# mrShark_04_a.net
KiCad netlist of a schematic drawn in EAGLE
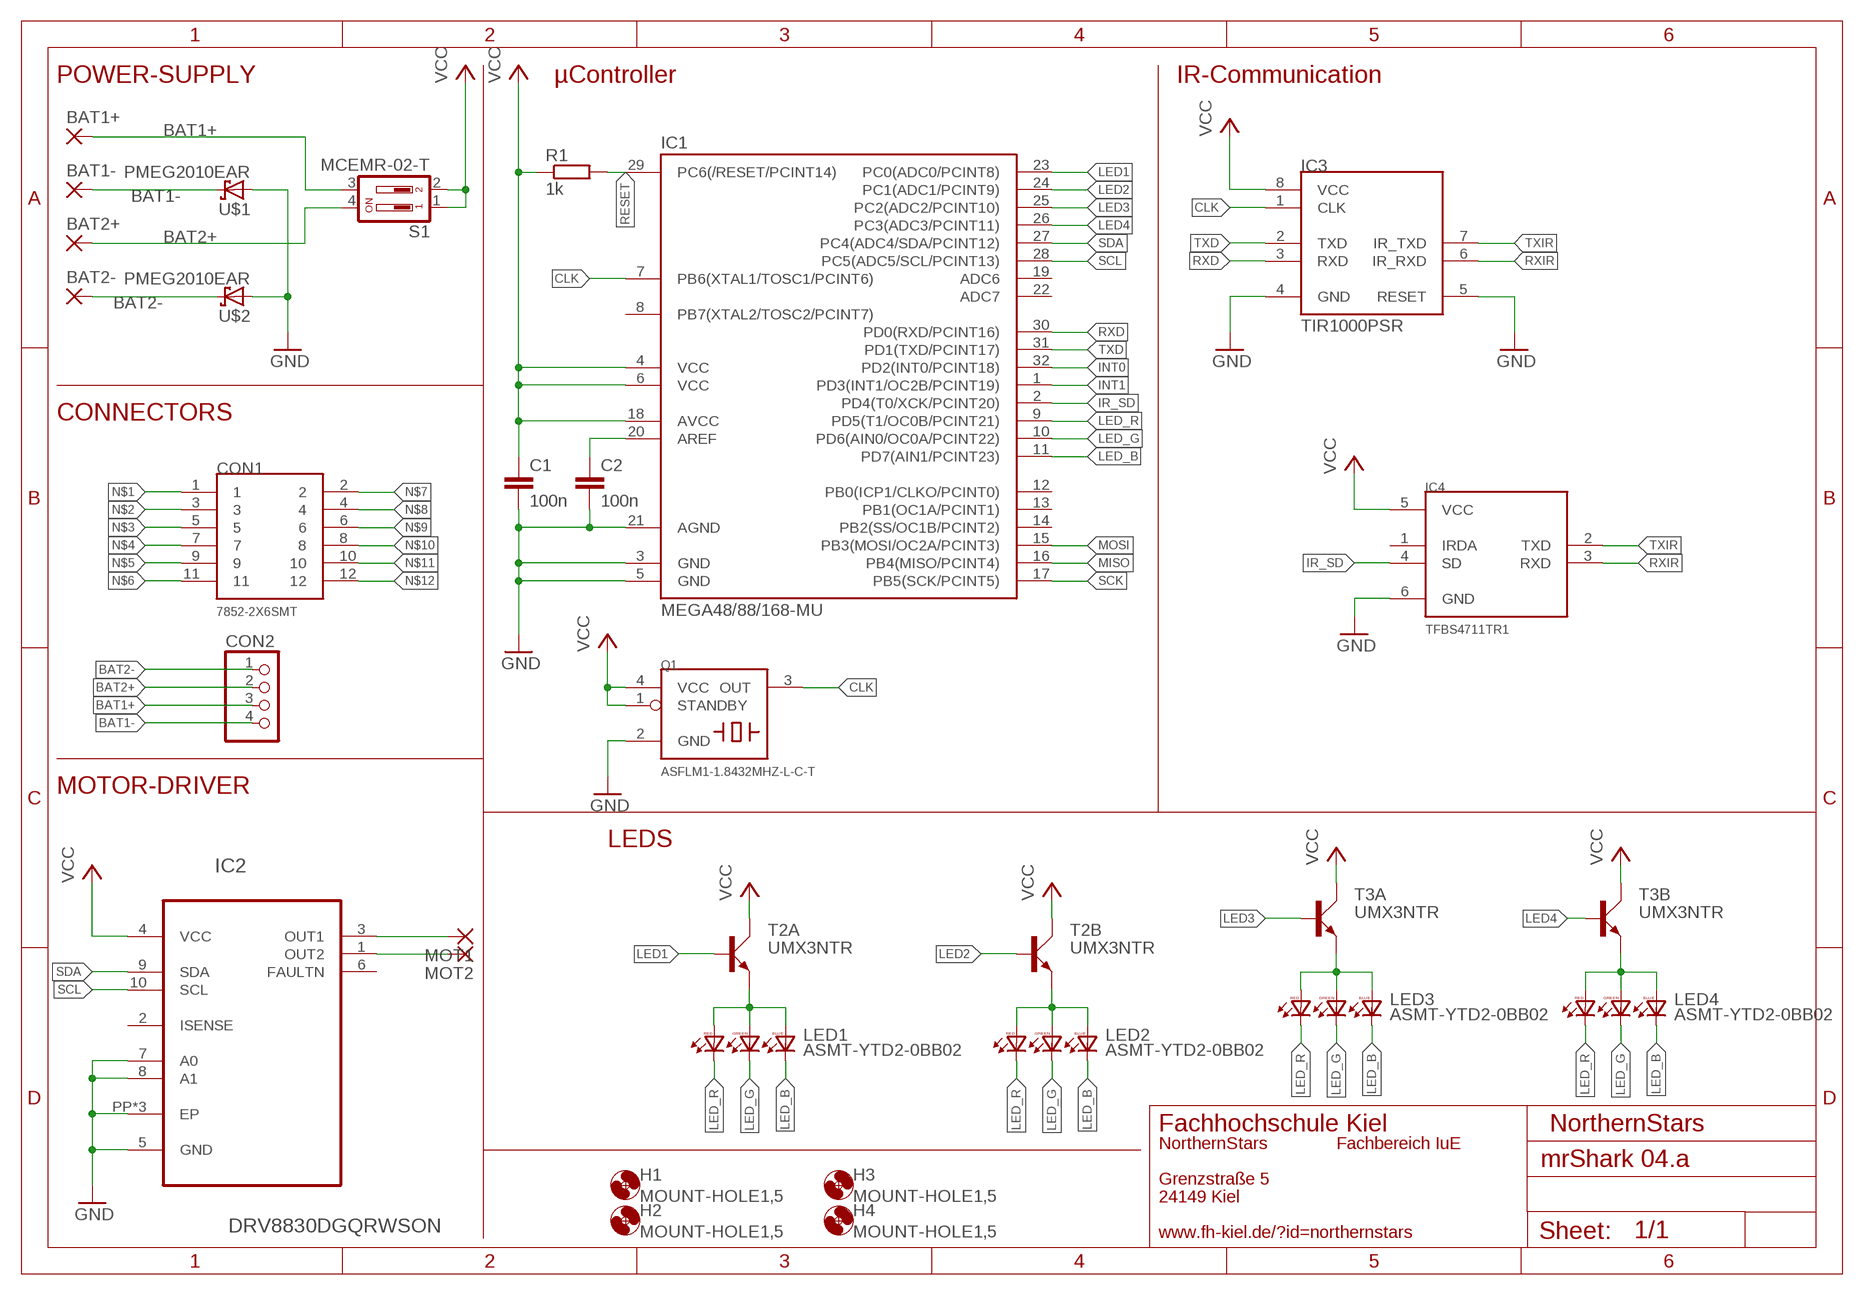
[diagram p0: schematic, sheet 1]

(export (version "E")
  (design (tool "Eeschema 10.0.6"))
  (components
    (comp (ref "BAT1+")
      (value "1,6/0,9")
      (footprint "eagle-import:1,6_0,9")
      (libsource (lib "eagle-import") (part "1,6/0,9"))
    )
    (comp (ref "BAT1-")
      (value "1,6/0,9")
      (footprint "eagle-import:1,6_0,9")
      (libsource (lib "eagle-import") (part "1,6/0,9"))
    )
    (comp (ref "BAT2+")
      (value "1,6/0,9")
      (footprint "eagle-import:1,6_0,9")
      (libsource (lib "eagle-import") (part "1,6/0,9"))
    )
    (comp (ref "BAT2-")
      (value "1,6/0,9")
      (footprint "eagle-import:1,6_0,9")
      (libsource (lib "eagle-import") (part "1,6/0,9"))
    )
    (comp (ref "C1")
      (value "100n")
      (footprint "eagle-import:C0201")
      (libsource (lib "eagle-import") (part "C-EUC0201"))
    )
    (comp (ref "C2")
      (value "100n")
      (footprint "eagle-import:C0201")
      (libsource (lib "eagle-import") (part "C-EUC0201"))
    )
    (comp (ref "CON1")
      (value "7852-2X6SMT")
      (footprint "eagle-import:7852-2X6")
      (libsource (lib "eagle-import") (part "7852-2X6SMT"))
    )
    (comp (ref "CON2")
      (value "PINHD-1X04_2.54-SMD-90°")
      (footprint "eagle-import:1X04SMD_90")
      (libsource (lib "eagle-import") (part "PINHD-1X04_2.54-SMD-90°"))
    )
    (comp (ref "H1")
      (value "MOUNT-HOLE1,5")
      (footprint "eagle-import:1,5")
      (libsource (lib "eagle-import") (part "MOUNT-HOLE1,5"))
    )
    (comp (ref "H2")
      (value "MOUNT-HOLE1,5")
      (footprint "eagle-import:1,5")
      (libsource (lib "eagle-import") (part "MOUNT-HOLE1,5"))
    )
    (comp (ref "H3")
      (value "MOUNT-HOLE1,5")
      (footprint "eagle-import:1,5")
      (libsource (lib "eagle-import") (part "MOUNT-HOLE1,5"))
    )
    (comp (ref "H4")
      (value "MOUNT-HOLE1,5")
      (footprint "eagle-import:1,5")
      (libsource (lib "eagle-import") (part "MOUNT-HOLE1,5"))
    )
    (comp (ref "IC1")
      (value "MEGA48/88/168-MU")
      (footprint "eagle-import:MLF32")
      (libsource (lib "eagle-import") (part "MEGA48/88/168-MU"))
    )
    (comp (ref "IC2")
      (value "DRV8830DGQRWSON")
      (footprint "eagle-import:S-PDSO-N10")
      (libsource (lib "eagle-import") (part "DRV8830DGQRWSON"))
    )
    (comp (ref "IC3")
      (value "TIR1000PSR")
      (footprint "eagle-import:SO-08")
      (libsource (lib "eagle-import") (part "TIR1000PSR"))
    )
    (comp (ref "IC4")
      (value "TFBS4711TR1")
      (footprint "eagle-import:TFBS4711")
      (libsource (lib "eagle-import") (part "TFBS4711TR1"))
    )
    (comp (ref "LED1")
      (value "ASMT-YTD2-0BB02")
      (footprint "eagle-import:PLCC6")
      (libsource (lib "eagle-import") (part "PLCC6"))
    )
    (comp (ref "LED2")
      (value "ASMT-YTD2-0BB02")
      (footprint "eagle-import:PLCC6")
      (libsource (lib "eagle-import") (part "PLCC6"))
    )
    (comp (ref "LED3")
      (value "ASMT-YTD2-0BB02")
      (footprint "eagle-import:PLCC6")
      (libsource (lib "eagle-import") (part "PLCC6"))
    )
    (comp (ref "LED4")
      (value "ASMT-YTD2-0BB02")
      (footprint "eagle-import:PLCC6")
      (libsource (lib "eagle-import") (part "PLCC6"))
    )
    (comp (ref "MOT1")
      (value "1,6/0,9")
      (footprint "eagle-import:1,6_0,9")
      (libsource (lib "eagle-import") (part "1,6/0,9"))
    )
    (comp (ref "MOT2")
      (value "1,6/0,9")
      (footprint "eagle-import:1,6_0,9")
      (libsource (lib "eagle-import") (part "1,6/0,9"))
    )
    (comp (ref "Q1")
      (value "ASFLM1-1.8432MHZ-L-C-T")
      (footprint "eagle-import:MEMS")
      (libsource (lib "eagle-import") (part "MEMS'-SMD"))
    )
    (comp (ref "R1")
      (value "1k")
      (footprint "eagle-import:R0201")
      (libsource (lib "eagle-import") (part "R-EU_R0201"))
    )
    (comp (ref "S1")
      (value "MCEMR-02-T")
      (footprint "eagle-import:CTS-219-02")
      (libsource (lib "eagle-import") (part "219-02"))
    )
    (comp (ref "T2")
      (value "UMX3NTR")
      (footprint "eagle-import:SOT363_INFINEON")
      (libsource (lib "eagle-import") (part "UMX3NTR-SOT363"))
    )
    (comp (ref "T3")
      (value "UMX3NTR")
      (footprint "eagle-import:SOT363_INFINEON")
      (libsource (lib "eagle-import") (part "UMX3NTR-SOT363"))
    )
    (comp (ref "U$1")
      (value "PMEG2010EAR")
      (footprint "eagle-import:SOD323-R")
      (libsource (lib "eagle-import") (part "PMEG2010EAR"))
    )
    (comp (ref "U$2")
      (value "PMEG2010EAR")
      (footprint "eagle-import:SOD323-R")
      (libsource (lib "eagle-import") (part "PMEG2010EAR"))
    )
  )
  (nets
    (net (code "1") (name "BAT1+") (class "Default")
      (node (ref "BAT1+") (pin "1") (pinfunction "P_1") (pintype "passive"))
      (node (ref "CON2") (pin "3") (pinfunction "3_3") (pintype "passive"))
      (node (ref "S1") (pin "3") (pinfunction "3_3") (pintype "passive"))
    )
    (net (code "2") (name "BAT1-") (class "Default")
      (node (ref "BAT1-") (pin "1") (pinfunction "P_1") (pintype "passive"))
      (node (ref "CON2") (pin "4") (pinfunction "4_4") (pintype "passive"))
      (node (ref "U$1") (pin "C") (pinfunction "C_C") (pintype "passive"))
    )
    (net (code "3") (name "BAT2+") (class "Default")
      (node (ref "BAT2+") (pin "1") (pinfunction "P_1") (pintype "passive"))
      (node (ref "CON2") (pin "2") (pinfunction "2_2") (pintype "passive"))
      (node (ref "S1") (pin "4") (pinfunction "4_4") (pintype "passive"))
    )
    (net (code "4") (name "BAT2-") (class "Default")
      (node (ref "BAT2-") (pin "1") (pinfunction "P_1") (pintype "passive"))
      (node (ref "CON2") (pin "1") (pinfunction "1_1") (pintype "passive"))
      (node (ref "U$2") (pin "C") (pinfunction "C_C") (pintype "passive"))
    )
    (net (code "5") (name "CLK") (class "Default")
      (node (ref "IC1") (pin "7") (pinfunction "PB6(XTAL1/TOSC1/PCINT6)_7") (pintype "bidirectional"))
      (node (ref "IC3") (pin "1") (pinfunction "CLK_1") (pintype "bidirectional"))
      (node (ref "Q1") (pin "3") (pinfunction "OUT_3") (pintype "bidirectional"))
    )
    (net (code "6") (name "GND") (class "Default")
      (node (ref "C1") (pin "2") (pinfunction "2_2") (pintype "passive"))
      (node (ref "C2") (pin "2") (pinfunction "2_2") (pintype "passive"))
      (node (ref "IC1") (pin "21") (pinfunction "AGND_21") (pintype "power_in"))
      (node (ref "IC1") (pin "3") (pinfunction "GND_3") (pintype "power_in"))
      (node (ref "IC1") (pin "5") (pinfunction "GND_5") (pintype "power_in"))
      (node (ref "IC2") (pin "5") (pinfunction "GND_5") (pintype "passive"))
      (node (ref "IC2") (pin "7") (pinfunction "A0_7") (pintype "input"))
      (node (ref "IC2") (pin "8") (pinfunction "A1_8") (pintype "input"))
      (node (ref "IC2") (pin "PP") (pinfunction "EP_PP") (pintype "passive"))
      (node (ref "IC2") (pin "PP@1") (pinfunction "EP_PP@1") (pintype "passive"))
      (node (ref "IC2") (pin "PP@2") (pinfunction "EP_PP@2") (pintype "passive"))
      (node (ref "IC3") (pin "4") (pinfunction "GND_4") (pintype "bidirectional"))
      (node (ref "IC3") (pin "5") (pinfunction "RESET_5") (pintype "bidirectional"))
      (node (ref "IC4") (pin "6") (pinfunction "GND_6") (pintype "bidirectional"))
      (node (ref "Q1") (pin "2") (pinfunction "GND_2") (pintype "bidirectional"))
      (node (ref "U$1") (pin "A") (pinfunction "A_A") (pintype "passive"))
      (node (ref "U$2") (pin "A") (pinfunction "A_A") (pintype "passive"))
    )
    (net (code "7") (name "INT0") (class "Default")
      (node (ref "IC1") (pin "32") (pinfunction "PD2(INT0/PCINT18)_32") (pintype "bidirectional"))
    )
    (net (code "8") (name "INT1") (class "Default")
      (node (ref "IC1") (pin "1") (pinfunction "PD3(INT1/OC2B/PCINT19)_1") (pintype "bidirectional"))
    )
    (net (code "9") (name "IR_SD") (class "Default")
      (node (ref "IC1") (pin "2") (pinfunction "PD4(T0/XCK/PCINT20)_2") (pintype "bidirectional"))
      (node (ref "IC4") (pin "4") (pinfunction "SD_4") (pintype "bidirectional"))
    )
    (net (code "10") (name "LED1") (class "Default")
      (node (ref "IC1") (pin "23") (pinfunction "PC0(ADC0/PCINT8)_23") (pintype "bidirectional"))
      (node (ref "T2") (pin "2") (pinfunction "B_2") (pintype "passive"))
    )
    (net (code "11") (name "LED2") (class "Default")
      (node (ref "IC1") (pin "24") (pinfunction "PC1(ADC1/PCINT9)_24") (pintype "bidirectional"))
      (node (ref "T2") (pin "3") (pinfunction "B_3") (pintype "passive"))
    )
    (net (code "12") (name "LED3") (class "Default")
      (node (ref "IC1") (pin "25") (pinfunction "PC2(ADC2/PCINT10)_25") (pintype "bidirectional"))
      (node (ref "T3") (pin "2") (pinfunction "B_2") (pintype "passive"))
    )
    (net (code "13") (name "LED4") (class "Default")
      (node (ref "IC1") (pin "26") (pinfunction "PC3(ADC3/PCINT11)_26") (pintype "bidirectional"))
      (node (ref "T3") (pin "3") (pinfunction "B_3") (pintype "passive"))
    )
    (net (code "14") (name "LED_B") (class "Default")
      (node (ref "IC1") (pin "11") (pinfunction "PD7(AIN1/PCINT23)_11") (pintype "bidirectional"))
      (node (ref "LED1") (pin "1") (pinfunction "BC_1") (pintype "passive"))
      (node (ref "LED2") (pin "1") (pinfunction "BC_1") (pintype "passive"))
      (node (ref "LED3") (pin "1") (pinfunction "BC_1") (pintype "passive"))
      (node (ref "LED4") (pin "1") (pinfunction "BC_1") (pintype "passive"))
    )
    (net (code "15") (name "LED_G") (class "Default")
      (node (ref "IC1") (pin "10") (pinfunction "PD6(AIN0/OC0A/PCINT22)_10") (pintype "bidirectional"))
      (node (ref "LED1") (pin "2") (pinfunction "GC_2") (pintype "passive"))
      (node (ref "LED2") (pin "2") (pinfunction "GC_2") (pintype "passive"))
      (node (ref "LED3") (pin "2") (pinfunction "GC_2") (pintype "passive"))
      (node (ref "LED4") (pin "2") (pinfunction "GC_2") (pintype "passive"))
    )
    (net (code "16") (name "LED_R") (class "Default")
      (node (ref "IC1") (pin "9") (pinfunction "PD5(T1/OC0B/PCINT21)_9") (pintype "bidirectional"))
      (node (ref "LED1") (pin "3") (pinfunction "RC_3") (pintype "passive"))
      (node (ref "LED2") (pin "3") (pinfunction "RC_3") (pintype "passive"))
      (node (ref "LED3") (pin "3") (pinfunction "RC_3") (pintype "passive"))
      (node (ref "LED4") (pin "3") (pinfunction "RC_3") (pintype "passive"))
    )
    (net (code "17") (name "MISO") (class "Default")
      (node (ref "IC1") (pin "16") (pinfunction "PB4(MISO/PCINT4)_16") (pintype "bidirectional"))
    )
    (net (code "18") (name "MOSI") (class "Default")
      (node (ref "IC1") (pin "15") (pinfunction "PB3(MOSI/OC2A/PCINT3)_15") (pintype "bidirectional"))
    )
    (net (code "19") (name "N$1") (class "Default")
      (node (ref "CON1") (pin "1") (pinfunction "1_1") (pintype "bidirectional"))
    )
    (net (code "20") (name "N$2") (class "Default")
      (node (ref "CON1") (pin "3") (pinfunction "3_3") (pintype "bidirectional"))
    )
    (net (code "21") (name "N$3") (class "Default")
      (node (ref "CON1") (pin "5") (pinfunction "5_5") (pintype "bidirectional"))
    )
    (net (code "22") (name "N$4") (class "Default")
      (node (ref "CON1") (pin "7") (pinfunction "7_7") (pintype "bidirectional"))
    )
    (net (code "23") (name "N$5") (class "Default")
      (node (ref "CON1") (pin "9") (pinfunction "9_9") (pintype "bidirectional"))
    )
    (net (code "24") (name "N$6") (class "Default")
      (node (ref "CON1") (pin "11") (pinfunction "11_11") (pintype "bidirectional"))
    )
    (net (code "25") (name "N$7") (class "Default")
      (node (ref "CON1") (pin "2") (pinfunction "2_2") (pintype "bidirectional"))
    )
    (net (code "26") (name "N$8") (class "Default")
      (node (ref "CON1") (pin "4") (pinfunction "4_4") (pintype "bidirectional"))
    )
    (net (code "27") (name "N$9") (class "Default")
      (node (ref "CON1") (pin "6") (pinfunction "6_6") (pintype "bidirectional"))
    )
    (net (code "28") (name "N$10") (class "Default")
      (node (ref "CON1") (pin "8") (pinfunction "8_8") (pintype "bidirectional"))
    )
    (net (code "29") (name "N$11") (class "Default")
      (node (ref "CON1") (pin "10") (pinfunction "10_10") (pintype "bidirectional"))
    )
    (net (code "30") (name "N$12") (class "Default")
      (node (ref "CON1") (pin "12") (pinfunction "12_12") (pintype "bidirectional"))
    )
    (net (code "31") (name "Net-(IC1-AREF)") (class "Default")
      (node (ref "C2") (pin "1") (pinfunction "1_1") (pintype "passive"))
      (node (ref "IC1") (pin "20") (pinfunction "AREF_20") (pintype "passive"))
    )
    (net (code "32") (name "Net-(IC2-OUT1)") (class "Default")
      (node (ref "IC2") (pin "3") (pinfunction "OUT1_3") (pintype "output"))
      (node (ref "MOT1") (pin "1") (pinfunction "P_1") (pintype "passive"))
    )
    (net (code "33") (name "Net-(IC2-OUT2)") (class "Default")
      (node (ref "IC2") (pin "1") (pinfunction "OUT2_1") (pintype "output"))
      (node (ref "MOT2") (pin "1") (pinfunction "P_1") (pintype "passive"))
    )
    (net (code "34") (name "Net-(LED1-BA)") (class "Default")
      (node (ref "LED1") (pin "4") (pinfunction "RA_4") (pintype "passive"))
      (node (ref "LED1") (pin "5") (pinfunction "GA_5") (pintype "passive"))
      (node (ref "LED1") (pin "6") (pinfunction "BA_6") (pintype "passive"))
      (node (ref "T2") (pin "1") (pinfunction "E_1") (pintype "passive"))
    )
    (net (code "35") (name "Net-(LED2-BA)") (class "Default")
      (node (ref "LED2") (pin "4") (pinfunction "RA_4") (pintype "passive"))
      (node (ref "LED2") (pin "5") (pinfunction "GA_5") (pintype "passive"))
      (node (ref "LED2") (pin "6") (pinfunction "BA_6") (pintype "passive"))
      (node (ref "T2") (pin "5") (pinfunction "E_5") (pintype "passive"))
    )
    (net (code "36") (name "Net-(LED3-BA)") (class "Default")
      (node (ref "LED3") (pin "4") (pinfunction "RA_4") (pintype "passive"))
      (node (ref "LED3") (pin "5") (pinfunction "GA_5") (pintype "passive"))
      (node (ref "LED3") (pin "6") (pinfunction "BA_6") (pintype "passive"))
      (node (ref "T3") (pin "1") (pinfunction "E_1") (pintype "passive"))
    )
    (net (code "37") (name "Net-(LED4-BA)") (class "Default")
      (node (ref "LED4") (pin "4") (pinfunction "RA_4") (pintype "passive"))
      (node (ref "LED4") (pin "5") (pinfunction "GA_5") (pintype "passive"))
      (node (ref "LED4") (pin "6") (pinfunction "BA_6") (pintype "passive"))
      (node (ref "T3") (pin "5") (pinfunction "E_5") (pintype "passive"))
    )
    (net (code "38") (name "RESET") (class "Default")
      (node (ref "IC1") (pin "29") (pinfunction "PC6(/RESET/PCINT14)_29") (pintype "bidirectional"))
      (node (ref "R1") (pin "2") (pinfunction "2_2") (pintype "passive"))
    )
    (net (code "39") (name "RXD") (class "Default")
      (node (ref "IC1") (pin "30") (pinfunction "PD0(RXD/PCINT16)_30") (pintype "bidirectional"))
      (node (ref "IC3") (pin "3") (pinfunction "RXD_3") (pintype "bidirectional"))
    )
    (net (code "40") (name "RXIR") (class "Default")
      (node (ref "IC3") (pin "6") (pinfunction "IR_RXD_6") (pintype "bidirectional"))
      (node (ref "IC4") (pin "3") (pinfunction "RXD_3") (pintype "output"))
    )
    (net (code "41") (name "SCK") (class "Default")
      (node (ref "IC1") (pin "17") (pinfunction "PB5(SCK/PCINT5)_17") (pintype "bidirectional"))
    )
    (net (code "42") (name "SCL") (class "Default")
      (node (ref "IC1") (pin "28") (pinfunction "PC5(ADC5/SCL/PCINT13)_28") (pintype "bidirectional"))
      (node (ref "IC2") (pin "10") (pinfunction "SCL_10") (pintype "input"))
    )
    (net (code "43") (name "SDA") (class "Default")
      (node (ref "IC1") (pin "27") (pinfunction "PC4(ADC4/SDA/PCINT12)_27") (pintype "bidirectional"))
      (node (ref "IC2") (pin "9") (pinfunction "SDA_9") (pintype "bidirectional"))
    )
    (net (code "44") (name "TXD") (class "Default")
      (node (ref "IC1") (pin "31") (pinfunction "PD1(TXD/PCINT17)_31") (pintype "bidirectional"))
      (node (ref "IC3") (pin "2") (pinfunction "TXD_2") (pintype "bidirectional"))
    )
    (net (code "45") (name "TXIR") (class "Default")
      (node (ref "IC3") (pin "7") (pinfunction "IR_TXD_7") (pintype "bidirectional"))
      (node (ref "IC4") (pin "2") (pinfunction "TXD_2") (pintype "input"))
    )
    (net (code "46") (name "VCC") (class "Default")
      (node (ref "C1") (pin "1") (pinfunction "1_1") (pintype "passive"))
      (node (ref "IC1") (pin "18") (pinfunction "AVCC_18") (pintype "passive"))
      (node (ref "IC1") (pin "4") (pinfunction "VCC_4") (pintype "power_in"))
      (node (ref "IC1") (pin "6") (pinfunction "VCC_6") (pintype "power_in"))
      (node (ref "IC2") (pin "4") (pinfunction "VCC_4") (pintype "power_in"))
      (node (ref "IC3") (pin "8") (pinfunction "VCC_8") (pintype "bidirectional"))
      (node (ref "IC4") (pin "5") (pinfunction "VCC_5") (pintype "power_in"))
      (node (ref "Q1") (pin "1") (pinfunction "STANDBY_1") (pintype "bidirectional"))
      (node (ref "Q1") (pin "4") (pinfunction "VCC_4") (pintype "bidirectional"))
      (node (ref "R1") (pin "1") (pinfunction "1_1") (pintype "passive"))
      (node (ref "S1") (pin "1") (pinfunction "1_1") (pintype "passive"))
      (node (ref "S1") (pin "2") (pinfunction "2_2") (pintype "passive"))
      (node (ref "T2") (pin "4") (pinfunction "C_4") (pintype "passive"))
      (node (ref "T2") (pin "6") (pinfunction "C_6") (pintype "passive"))
      (node (ref "T3") (pin "4") (pinfunction "C_4") (pintype "passive"))
      (node (ref "T3") (pin "6") (pinfunction "C_6") (pintype "passive"))
    )
    (net (code "47") (name "unconnected-(IC1-ADC6-Pad19)") (class "Default")
      (node (ref "IC1") (pin "19") (pinfunction "ADC6_19") (pintype "passive"))
    )
    (net (code "48") (name "unconnected-(IC1-ADC7-Pad22)") (class "Default")
      (node (ref "IC1") (pin "22") (pinfunction "ADC7_22") (pintype "passive"))
    )
    (net (code "49") (name "unconnected-(IC1-PB0(ICP1{slash}CLKO{slash}PCINT0)-Pad12)") (class "Default")
      (node (ref "IC1") (pin "12") (pinfunction "PB0(ICP1/CLKO/PCINT0)_12") (pintype "bidirectional"))
    )
    (net (code "50") (name "unconnected-(IC1-PB1(OC1A{slash}PCINT1)-Pad13)") (class "Default")
      (node (ref "IC1") (pin "13") (pinfunction "PB1(OC1A/PCINT1)_13") (pintype "bidirectional"))
    )
    (net (code "51") (name "unconnected-(IC1-PB2(SS{slash}OC1B{slash}PCINT2)-Pad14)") (class "Default")
      (node (ref "IC1") (pin "14") (pinfunction "PB2(SS/OC1B/PCINT2)_14") (pintype "bidirectional"))
    )
    (net (code "52") (name "unconnected-(IC1-PB7(XTAL2{slash}TOSC2{slash}PCINT7)-Pad8)") (class "Default")
      (node (ref "IC1") (pin "8") (pinfunction "PB7(XTAL2/TOSC2/PCINT7)_8") (pintype "bidirectional"))
    )
    (net (code "53") (name "unconnected-(IC2-FAULTN-Pad6)") (class "Default")
      (node (ref "IC2") (pin "6") (pinfunction "FAULTN_6") (pintype "output"))
    )
    (net (code "54") (name "unconnected-(IC2-ISENSE-Pad2)") (class "Default")
      (node (ref "IC2") (pin "2") (pinfunction "ISENSE_2") (pintype "input"))
    )
    (net (code "55") (name "unconnected-(IC4-IRDA-Pad1)") (class "Default")
      (node (ref "IC4") (pin "1") (pinfunction "IRDA_1") (pintype "bidirectional"))
    )
  )
)
